# PowerSchem.net
KiCad netlist of a schematic drawn in Altium Designer
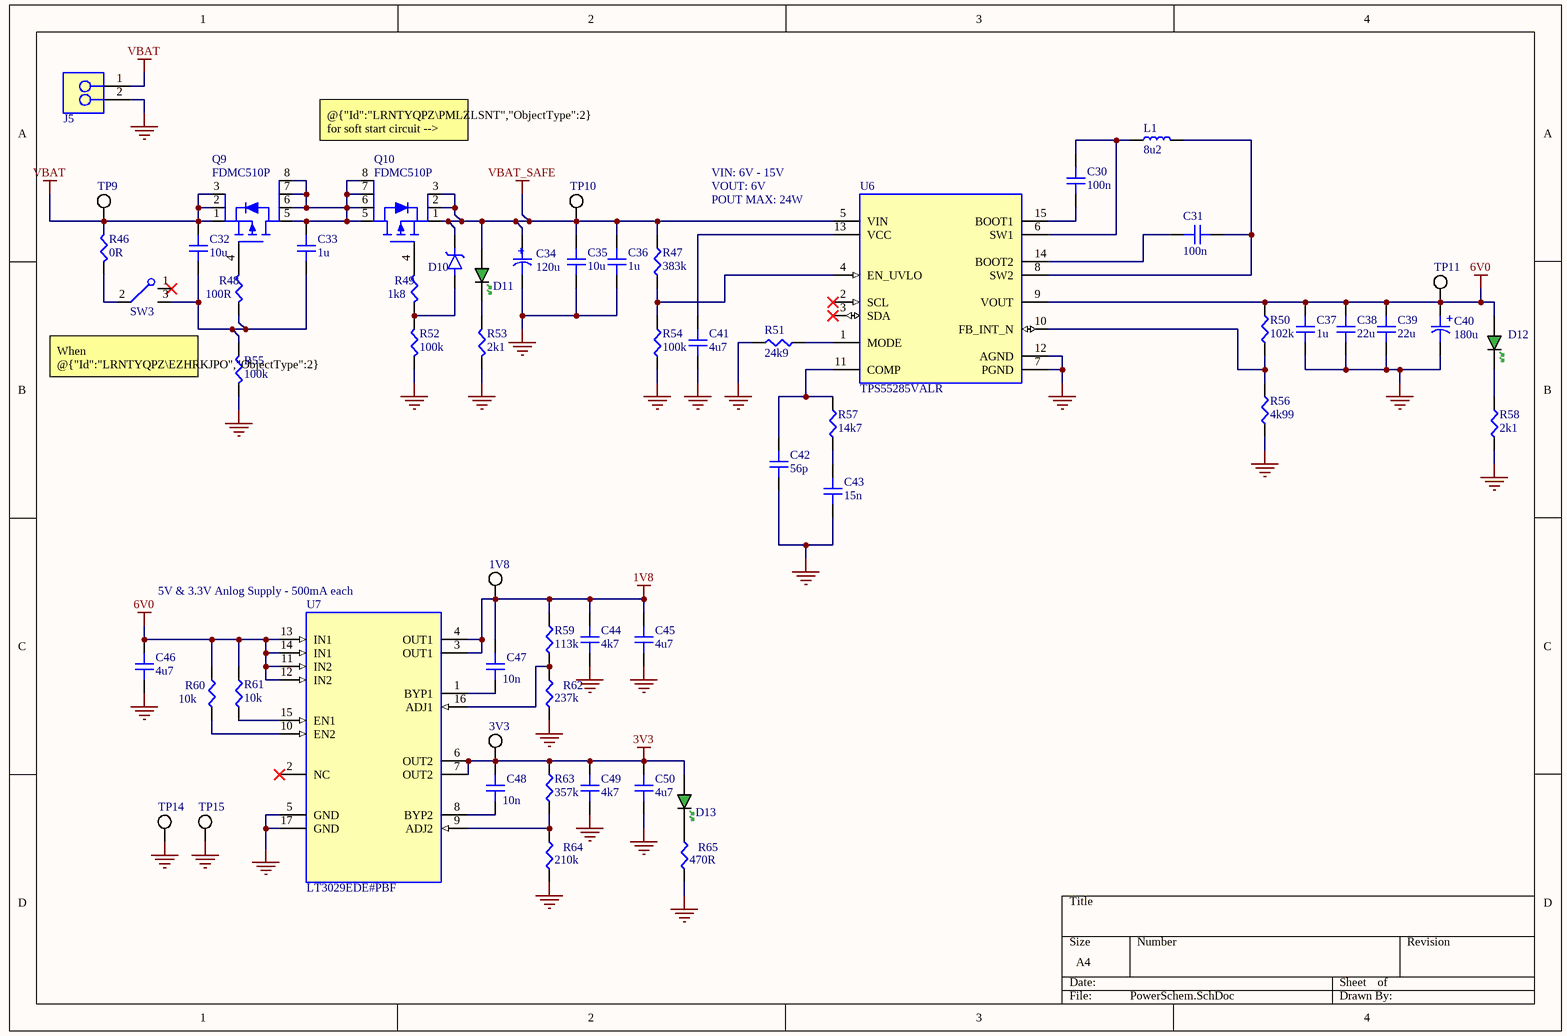
[diagram p0: PowerSchem.SchDoc]

(export (version "E")
  (design (tool "Eeschema 10.0.6"))
  (components
    (comp (ref "C30")
      (value "100n")
      (footprint "CAP_0603")
      (description "50V 100nF X7R ±10% 0603 Multilayer Ceramic Capacitors MLCC - SMD/SMT ROHS")
      (fields
        (field (name "MANUFACTURER") "Yageo Group")
        (field (name "MANUFACTURER PART NUMBER") "C0603C104K5RACTU")
      )
      (libsource (lib "Standard") (part "CAP"))
    )
    (comp (ref "C31")
      (value "100n")
      (footprint "CAP_0603")
      (description "50V 100nF X7R ±10% 0603 Multilayer Ceramic Capacitors MLCC - SMD/SMT ROHS")
      (fields (field (name "VOLTAGE") "50V") (field (name "MANUFACTURER") "Yageo Group"))
      (libsource (lib "Standard") (part "CAP"))
    )
    (comp (ref "C32")
      (value "10u")
      (footprint "CAP_0805")
      (description "25V 10uF X5R ±20% 0805 Multilayer Ceramic Capacitors MLCC - SMD/SMT ROHS")
      (fields
        (field (name "MANUFACTURER") "Murata")
        (field (name "MANUFACTURER PART NUMBER") "GRM21BR61E106MA73L")
      )
      (libsource (lib "Standard") (part "CAP"))
    )
    (comp (ref "C33")
      (value "1u")
      (footprint "CAP_0603")
      (description "25V 1uF X7R 卤10% 0603 Multilayer Ceramic Capacitors MLCC - SMD/SMT ROHS")
      (fields
        (field (name "MANUFACTURER") "Samsung Electro-Mechanics")
        (field (name "MANUFACTURER PART NUMBER") "CL10B105KA8NNNC")
      )
      (libsource (lib "Standard") (part "CAP"))
    )
    (comp (ref "C34")
      (value "120u")
      (footprint "PCAP_SVP_C6_PAN-M")
      (description "Cap Aluminum Polymer 120uF 20VDC 20%( 6.3 X 5.9mm) SMD 0.025 Ohm 3.2A 5000h 105C T/R")
      (fields
        (field (name "MANUFACTURER") "Panasonic")
        (field (name "MANUFACTURER PART NUMBER") "20SVPF120M")
      )
      (libsource (lib "") (part "CAP_ELECTROLYTIC_1"))
    )
    (comp (ref "C35")
      (value "10u")
      (footprint "CAP_0805")
      (description "25V 10uF X5R ±20% 0805 Multilayer Ceramic Capacitors MLCC - SMD/SMT ROHS")
      (fields
        (field (name "MANUFACTURER") "Murata")
        (field (name "MANUFACTURER PART NUMBER") "GRM21BR61E106MA73L")
      )
      (libsource (lib "Standard") (part "CAP"))
    )
    (comp (ref "C36")
      (value "1u")
      (footprint "CAP_0603")
      (description "25V 1uF X7R 卤10% 0603 Multilayer Ceramic Capacitors MLCC - SMD/SMT ROHS")
      (fields
        (field (name "MANUFACTURER") "Samsung Electro-Mechanics")
        (field (name "MANUFACTURER PART NUMBER") "CL10B105KA8NNNC")
      )
      (libsource (lib "Standard") (part "CAP"))
    )
    (comp (ref "C37")
      (value "1u")
      (footprint "CAP_0603")
      (description "25V 1uF X7R 卤10% 0603 Multilayer Ceramic Capacitors MLCC - SMD/SMT ROHS")
      (fields
        (field (name "MANUFACTURER") "Samsung Electro-Mechanics")
        (field (name "MANUFACTURER PART NUMBER") "CL10B105KA8NNNC")
      )
      (libsource (lib "Standard") (part "CAP"))
    )
    (comp (ref "C38")
      (value "22u")
      (footprint "CAP_0805")
      (description "25V 22uF X5R 卤20% 0805 Multilayer Ceramic Capacitors MLCC - SMD/SMT ROHS")
      (fields
        (field (name "MANUFACTURER") "Samsung Electro-Mechanics")
        (field (name "MANUFACTURER PART NUMBER") "CL21A226MAYNNNE")
      )
      (libsource (lib "Standard") (part "CAP"))
    )
    (comp (ref "C39")
      (value "22u")
      (footprint "CAP_0805")
      (description "25V 22uF X5R 卤20% 0805 Multilayer Ceramic Capacitors MLCC - SMD/SMT ROHS")
      (fields
        (field (name "MANUFACTURER") "Samsung Electro-Mechanics")
        (field (name "MANUFACTURER PART NUMBER") "CL21A226MAYNNNE")
      )
      (libsource (lib "Standard") (part "CAP"))
    )
    (comp (ref "C40")
      (value "180u")
      (footprint "PCAP_SVP_C6_PAN-M")
      (description "Cap Aluminum Polymer 180uF 16VDC 20%( 6.3 X 5.9mm) SMD 0.022 Ohm 3.3A 5000h 105C T/R")
      (fields
        (field (name "MANUFACTURER") "Panasonic")
        (field (name "MANUFACTURER PART NUMBER") "16SVPF180M")
      )
      (libsource (lib "Standard") (part "CAP_ELECTROLYTIC"))
    )
    (comp (ref "C41")
      (value "4u7")
      (footprint "CAP_0603")
      (description "25V 4.7uF X6S ±10% 0603 Multilayer Ceramic Capacitors MLCC - SMD/SMT ROHS")
      (fields
        (field (name "MANUFACTURER") "Murata")
        (field (name "MANUFACTURER PART NUMBER") "GRT188C81E475KE13D")
      )
      (libsource (lib "Standard") (part "CAP"))
    )
    (comp (ref "C42")
      (value "56p")
      (footprint "CAP_0603")
      (fields
        (field (name "MANUFACTURER") "Knowles")
        (field (name "MANUFACTURER PART NUMBER") "QSCP251Q560J1GV001T")
      )
      (libsource (lib "Standard") (part "CAP"))
    )
    (comp (ref "C43")
      (value "15n")
      (footprint "CAP_0603")
      (description "0603 C 15NF Ceramic Multilayer Capacitor, 25 V, +125DEGC, C0G Dielectric, +/-5%")
      (fields
        (field (name "MANUFACTURER") "Yageo Group")
        (field (name "MANUFACTURER PART NUMBER") "C0603C153J3GACTU")
      )
      (libsource (lib "Standard") (part "CAP"))
    )
    (comp (ref "C44")
      (value "4k7")
      (footprint "CAP_0603")
      (description "25V 4.7uF X6S ±10% 0603 Multilayer Ceramic Capacitors MLCC - SMD/SMT ROHS")
      (fields
        (field (name "MANUFACTURER") "Murata")
        (field (name "MANUFACTURER PART NUMBER") "GRT188C81E475KE13D")
      )
      (libsource (lib "Passives") (part "CAP"))
    )
    (comp (ref "C45")
      (value "4u7")
      (footprint "CAP_0603")
      (description "25V 4.7uF X6S ±10% 0603 Multilayer Ceramic Capacitors MLCC - SMD/SMT ROHS")
      (fields
        (field (name "MANUFACTURER") "Murata")
        (field (name "MANUFACTURER PART NUMBER") "GRT188C81E475KE13D")
      )
      (libsource (lib "Passives") (part "CAP"))
    )
    (comp (ref "C46")
      (value "4u7")
      (footprint "CAP_0603")
      (description "25V 4.7uF X6S ±10% 0603 Multilayer Ceramic Capacitors MLCC - SMD/SMT ROHS")
      (fields
        (field (name "MANUFACTURER") "Murata")
        (field (name "MANUFACTURER PART NUMBER") "GRT188C81E475KE13D")
      )
      (libsource (lib "Passives") (part "CAP"))
    )
    (comp (ref "C47")
      (value "10n")
      (footprint "CAP_0603")
      (description "Multilayer Ceramic Capacitors Mlcc - Smd/Smt 50V 0.01Uf X7R 0603 10%")
      (fields
        (field (name "MANUFACTURER") "Yageo Group")
        (field (name "MANUFACTURER PART NUMBER") "C0603C103K5RACTU")
      )
      (libsource (lib "Passives") (part "CAP"))
    )
    (comp (ref "C48")
      (value "10n")
      (footprint "CAP_0603")
      (description "Multilayer Ceramic Capacitors Mlcc - Smd/Smt 50V 0.01Uf X7R 0603 10%")
      (fields
        (field (name "MANUFACTURER") "Yageo Group")
        (field (name "MANUFACTURER PART NUMBER") "C0603C103K5RACTU")
      )
      (libsource (lib "Passives") (part "CAP"))
    )
    (comp (ref "C49")
      (value "4k7")
      (footprint "CAP_0603")
      (description "25V 4.7uF X6S ±10% 0603 Multilayer Ceramic Capacitors MLCC - SMD/SMT ROHS")
      (fields
        (field (name "MANUFACTURER") "Murata")
        (field (name "MANUFACTURER PART NUMBER") "GRT188C81E475KE13D")
      )
      (libsource (lib "Passives") (part "CAP"))
    )
    (comp (ref "C50")
      (value "4u7")
      (footprint "CAP_0603")
      (description "25V 4.7uF X6S ±10% 0603 Multilayer Ceramic Capacitors MLCC - SMD/SMT ROHS")
      (fields
        (field (name "MANUFACTURER") "Murata")
        (field (name "MANUFACTURER PART NUMBER") "GRT188C81E475KE13D")
      )
      (libsource (lib "Passives") (part "CAP"))
    )
    (comp (ref "D10")
      (value "65pF")
      (footprint "SOD-923")
      (description "ESD9X5.0ST5G Series 6.2 V 65 pF TVS Diode for ESD Protection - SOD-923")
      (fields (field (name "MANUFACTURER") "onsemi") (field (name "MANUFACTURER PART NUMBER") "ESD9X5.0ST5G"))
      (libsource (lib "Diodes") (part "Zenner"))
    )
    (comp (ref "D11")
      (value "LED_Green")
      (footprint "LED_0603")
      (description "LED yellow green 0603 wavelength 567.5~576.5nm light intensity 4.5~28mcd Front Mounting")
      (fields
        (field (name "MANUFACTURER") "Diodes Inc.")
        (field (name "MANUFACTURER PART NUMBER") "LTST-C193KGKT-5A")
      )
      (libsource (lib "Standard") (part "LED_Green"))
    )
    (comp (ref "D12")
      (value "LED_Green")
      (footprint "LED_0603")
      (description "LED yellow green 0603 wavelength 567.5~576.5nm light intensity 4.5~28mcd Front Mounting")
      (fields
        (field (name "MANUFACTURER") "Diodes Inc.")
        (field (name "MANUFACTURER PART NUMBER") "LTST-C193KGKT-5A")
      )
      (libsource (lib "Standard") (part "LED_Green"))
    )
    (comp (ref "D13")
      (value "LED_Green")
      (footprint "LED_0603")
      (description "LED yellow green 0603 wavelength 567.5~576.5nm light intensity 4.5~28mcd Front Mounting")
      (fields
        (field (name "MANUFACTURER") "Diodes Inc.")
        (field (name "MANUFACTURER PART NUMBER") "LTST-C193KGKT-5A")
      )
      (libsource (lib "Standard") (part "LED_Green"))
    )
    (comp (ref "J5")
      (value "2POS")
      (footprint "JST_B2B-XH-A")
      (description "Board Connector, 2 Contact(s), 1 Row(s), Male, Straight, Solder Terminal")
      (fields (field (name "MANUFACTURER") "JST") (field (name "MANUFACTURER PART NUMBER") "B2B-XH-A"))
      (libsource (lib "Connectors") (part "2POS"))
    )
    (comp (ref "L1")
      (value "8u2")
      (footprint "IND_SRP1265A-6R8M")
      (description "Ind Power Shielded Wirewound 8.2uH 20% 100kHz Metal Alloy Powder 8A (6.6 X 6.4 X 5.8mm) T/R")
      (fields
        (field (name "MANUFACTURER") "Bourns")
        (field (name "MANUFACTURER PART NUMBER") "SRP6060FA-8R2M")
      )
      (libsource (lib "Standard") (part "IND_FIXED"))
    )
    (comp (ref "Q9")
      (value "FDMC510P")
      (footprint "WDFN8_3.3X3.3")
      (description "Single P-Channel 20 V 17 mOhm 116 nC 41 W PowerTrench SMT Mosfet - MLP-3.3x3.3")
      (fields (field (name "MANUFACTURER") "onsemi"))
      (libsource (lib "Diodes") (part "PMOS"))
    )
    (comp (ref "Q10")
      (value "FDMC510P")
      (footprint "WDFN8_3.3X3.3")
      (description "Single P-Channel 20 V 17 mOhm 116 nC 41 W PowerTrench SMT Mosfet - MLP-3.3x3.3")
      (fields (field (name "MANUFACTURER") "onsemi"))
      (libsource (lib "Diodes") (part "PMOS"))
    )
    (comp (ref "R46")
      (value "0R")
      (footprint "RES_0603")
      (description "GENERAL PURPOSE CHIP RESISTOR Metal Glaze/thick Film, 0.1W, 0ohm, Surface Mount, 0603")
      (fields
        (field (name "MANUFACTURER") "Yageo Group")
        (field (name "MANUFACTURER PART NUMBER") "RC0603JR-070RL")
      )
      (libsource (lib "Passives") (part "RES"))
    )
    (comp (ref "R47")
      (value "383k")
      (footprint "RES_0603")
      (description "Res Thick Film 0603 383K Ohm 1% 0.1W(1/10W) ±100ppm/C Pad SMD T/R")
      (fields
        (field (name "MANUFACTURER") "Yageo Group")
        (field (name "MANUFACTURER PART NUMBER") "RC0603FR-07383KL")
      )
      (libsource (lib "Standard") (part "RES"))
    )
    (comp (ref "R48")
      (value "100R")
      (footprint "RES_0603")
      (description "Yageo RC0603FR-07100RL 0603 SMD Resistor 100 Ohm thin film chip resistor")
      (fields
        (field (name "MANUFACTURER") "Yageo Group")
        (field (name "MANUFACTURER PART NUMBER") "RC0603FR-07100RL")
      )
      (libsource (lib "Passives") (part "RES"))
    )
    (comp (ref "R49")
      (value "1k8")
      (footprint "RES_0603")
      (description "General Purpose Chip Resistors RC0603 Rohs Compliant ¦ Res SMD 1.8K Ohm 1% 1/10W 0603")
      (fields
        (field (name "MANUFACTURER") "Yageo Group")
        (field (name "MANUFACTURER PART NUMBER") "RC0603FR-071K8L")
      )
      (libsource (lib "Passives") (part "RES"))
    )
    (comp (ref "R50")
      (value "102k")
      (footprint "RES_0603")
      (description "100mW Thin Film Resistor ±25ppm/℃ ±0.1% 102kΩ 0603 Chip Resistor - Surface Mount ROHS")
      (fields
        (field (name "MANUFACTURER") "Yageo Group")
        (field (name "MANUFACTURER PART NUMBER") "RT0603BRD07102KL")
      )
      (libsource (lib "Standard") (part "RES"))
    )
    (comp (ref "R51")
      (value "24k9")
      (footprint "RES_0603")
      (description "Res Thick Film 0603 24.9K Ohm 1% 1/10W ¦100ppm/¦C SMD Punched Carrier T/R")
      (fields
        (field (name "MANUFACTURER") "Panasonic")
        (field (name "MANUFACTURER PART NUMBER") "ERJ-3EKF2492V")
      )
      (libsource (lib "Standard") (part "RES"))
    )
    (comp (ref "R52")
      (value "100k")
      (footprint "RES_0603")
      (description "Yageo RC0603FR-07100KL resistor 100k ohm 0603 1% thick film surface mount")
      (fields
        (field (name "MANUFACTURER") "Bourns")
        (field (name "MANUFACTURER PART NUMBER") "CR0603-FX-1003ELF")
      )
      (libsource (lib "Passives") (part "RES"))
    )
    (comp (ref "R53")
      (value "2k1")
      (footprint "RES_0603")
      (description "Res Thick Film 0603 2.1K Ohm 1% 0.1W(1/10W) ±100ppm/C Pad SMD T/R")
      (fields
        (field (name "MANUFACTURER") "Yageo Group")
        (field (name "MANUFACTURER PART NUMBER") "RC0603FR-072K1L")
      )
      (libsource (lib "Passives") (part "RES"))
    )
    (comp (ref "R54")
      (value "100k")
      (footprint "RES_0603")
      (description "Yageo RC0603FR-07100KL resistor 100k ohm 0603 1% thick film surface mount")
      (fields
        (field (name "MANUFACTURER") "Yageo Group")
        (field (name "MANUFACTURER PART NUMBER") "RC0603FR-07100KL")
      )
      (libsource (lib "Standard") (part "RES"))
    )
    (comp (ref "R55")
      (value "100k")
      (footprint "RES_0603")
      (description "Yageo RC0603FR-07100KL resistor 100k ohm 0603 1% thick film surface mount")
      (fields
        (field (name "MANUFACTURER") "Yageo Group")
        (field (name "MANUFACTURER PART NUMBER") "RC0603FR-07100KL")
      )
      (libsource (lib "Passives") (part "RES"))
    )
    (comp (ref "R56")
      (value "4k99")
      (footprint "RES_0603")
      (description "100mW Thick Film Resistors 75V ±100ppm/℃ ±1% 4.99kΩ 0603 Chip Resistor - Surface Mount ROHS")
      (fields
        (field (name "MANUFACTURER") "Yageo Group")
        (field (name "MANUFACTURER PART NUMBER") "RC0603FR-074K99L")
      )
      (libsource (lib "Standard") (part "RES"))
    )
    (comp (ref "R57")
      (value "14k7")
      (footprint "RES_0603")
      (description "Res Thick Film 0603 14.7K Ohm 1% 0.1W(1/10W) ±100ppm/C Pad SMD T/R Automotive AEC-Q200")
      (fields
        (field (name "MANUFACTURER") "Stackpole Electronics")
        (field (name "MANUFACTURER PART NUMBER") "RMCF0603FT14K7")
      )
      (libsource (lib "Standard") (part "RES"))
    )
    (comp (ref "R58")
      (value "2k1")
      (footprint "RES_0603")
      (description "Res Thick Film 0603 2.1K Ohm 1% 0.1W(1/10W) ±100ppm/C Pad SMD T/R")
      (fields
        (field (name "MANUFACTURER") "Yageo Group")
        (field (name "MANUFACTURER PART NUMBER") "RC0603FR-072K1L")
      )
      (libsource (lib "Standard") (part "RES"))
    )
    (comp (ref "R59")
      (value "113k")
      (footprint "RES_0603")
      (description "100mW Thick Film Resistors 75V ±100ppm/℃ ±1% 113kΩ 0603 Chip Resistor - Surface Mount ROHS")
      (fields
        (field (name "MANUFACTURER") "Yageo Group")
        (field (name "MANUFACTURER PART NUMBER") "RC0603FR-07113KL")
      )
      (libsource (lib "Passives") (part "RES"))
    )
    (comp (ref "R60")
      (value "10k")
      (footprint "RES_0603")
      (description "100mW Thick Film Resistors ±100ppm/℃ ±1% 10kΩ 0603 Chip Resistor - Surface Mount ROHS")
      (fields
        (field (name "MANUFACTURER") "Yageo Group")
        (field (name "MANUFACTURER PART NUMBER") "RC0603FR-0710KL")
      )
      (libsource (lib "Passives") (part "RES"))
    )
    (comp (ref "R61")
      (value "10k")
      (footprint "RES_0603")
      (description "100mW Thick Film Resistors ±100ppm/℃ ±1% 10kΩ 0603 Chip Resistor - Surface Mount ROHS")
      (fields
        (field (name "MANUFACTURER") "Yageo Group")
        (field (name "MANUFACTURER PART NUMBER") "RC0603FR-0710KL")
      )
      (libsource (lib "Passives") (part "RES"))
    )
    (comp (ref "R62")
      (value "237k")
      (footprint "RES_0603")
      (description "Res Thick Film 0603 237K Ohm 1% 0.1W(1/10W) ±100ppm/C Pad SMD Automotive T/R")
      (fields
        (field (name "MANUFACTURER") "Yageo Group")
        (field (name "MANUFACTURER PART NUMBER") "AC0603FR-07237KL")
      )
      (libsource (lib "Passives") (part "RES"))
    )
    (comp (ref "R63")
      (value "357k")
      (footprint "RES_0603")
      (description "Fixed Resistor, Thin Film, 0.1W, 357000ohm, 75V, 0.1% +/-Tol, 25ppm/Cel, Surface Mount, 0603")
      (fields
        (field (name "MANUFACTURER") "Yageo Group")
        (field (name "MANUFACTURER PART NUMBER") "RT0603BRD07357KL")
      )
      (libsource (lib "Passives") (part "RES"))
    )
    (comp (ref "R64")
      (value "210k")
      (footprint "RES_0603")
      (description "100mW Thick Film Resistors 75V ±100ppm/℃ ±1% 210kΩ 0603 Chip Resistor - Surface Mount ROHS")
      (fields
        (field (name "MANUFACTURER") "Yageo Group")
        (field (name "MANUFACTURER PART NUMBER") "RC0603FR-07210KL")
      )
      (libsource (lib "Passives") (part "RES"))
    )
    (comp (ref "R65")
      (value "470R")
      (footprint "RES_0603")
      (description "Res Thick Film 0603 470 Ohm 1% 0.1W(1/10W) ±100ppm/C Pad SMD T/R")
      (fields
        (field (name "MANUFACTURER") "Yageo Group")
        (field (name "MANUFACTURER PART NUMBER") "RC0603FR-07470RL")
      )
      (libsource (lib "Passives") (part "RES"))
    )
    (comp (ref "SW3")
      (value "SW_SPDT")
      (footprint "OS102011MA1QN1_CNK")
      (description "Switch Slide ON ON SPDT Side Slide 0.1A 12VDC 10000Cycle PC Pins Thru-Hole Bulk")
      (fields
        (field (name "MANUFACTURER") "C&K Components")
        (field (name "MANUFACTURER PART NUMBER") "OS102011MA1QN1")
      )
      (libsource (lib "Standard") (part "SW_SPDT"))
    )
    (comp (ref "TP9") (value "GND") (footprint "TP-TH") (libsource (lib "Passives") (part "TP")))
    (comp (ref "TP10") (value "GND") (footprint "TP-TH") (libsource (lib "Passives") (part "TP")))
    (comp (ref "TP11") (value "GND") (footprint "TP-TH") (libsource (lib "Passives") (part "TP")))
    (comp (ref "TP12") (value "1V8") (footprint "TP-TH") (libsource (lib "Passives") (part "TP")))
    (comp (ref "TP13") (value "3V3") (footprint "TP-TH") (libsource (lib "Passives") (part "TP")))
    (comp (ref "TP14") (value "GND") (footprint "TP-TH") (libsource (lib "Passives") (part "TP")))
    (comp (ref "TP15") (value "GND") (footprint "TP-TH") (libsource (lib "Passives") (part "TP")))
    (comp (ref "U6")
      (value "TPS55285VALR")
      (footprint "WQFN-HF(VAL)")
      (description "22V 8A buck-boost converter with I²C interface 15-WQFN-HR -40 to 125")
      (fields
        (field (name "MANUFACTURER_PART_NUMBER") "XTPS55285VALR")
        (field (name "MANUFACTURER") "Texas Instruments")
        (field (name "COPYRIGHT") "Copyright (C) 2026 Ultra Librarian. All rights reserved.")
      )
      (libsource (lib "Power") (part "XTPS55285VALR"))
    )
    (comp (ref "U7")
      (value "LT3029EDE#PBF")
      (footprint "MSOP-16_MSE")
      (description "LDO Regulator Pos 1.215V to 19.5V 0.5A 16-Pin DFN EP")
      (fields (field (name "MANUFACTURER") "Analog Devices"))
      (libsource (lib "Power") (part "LT3029EDE#PBF"))
    )
  )
  (nets
    (net (code "1") (name "1V8") (class "Default")
      (node (ref "C44") (pin "2") (pinfunction "2_2") (pintype "passive"))
      (node (ref "C45") (pin "2") (pinfunction "2_2") (pintype "passive"))
      (node (ref "C47") (pin "2") (pinfunction "2_2") (pintype "passive"))
      (node (ref "R59") (pin "2") (pinfunction "2_2") (pintype "passive"))
      (node (ref "TP12") (pin "1") (pinfunction "1_1") (pintype "passive"))
      (node (ref "U7") (pin "3") (pinfunction "OUT1_3") (pintype "power_in"))
      (node (ref "U7") (pin "4") (pinfunction "OUT1_4") (pintype "power_in"))
    )
    (net (code "2") (name "3V3") (class "Default")
      (node (ref "C48") (pin "2") (pinfunction "2_2") (pintype "passive"))
      (node (ref "C49") (pin "2") (pinfunction "2_2") (pintype "passive"))
      (node (ref "C50") (pin "2") (pinfunction "2_2") (pintype "passive"))
      (node (ref "D13") (pin "2") (pinfunction "Anode_2") (pintype "passive"))
      (node (ref "R63") (pin "2") (pinfunction "2_2") (pintype "passive"))
      (node (ref "TP13") (pin "1") (pinfunction "1_1") (pintype "passive"))
      (node (ref "U7") (pin "6") (pinfunction "OUT2_6") (pintype "power_in"))
      (node (ref "U7") (pin "7") (pinfunction "OUT2_7") (pintype "power_in"))
    )
    (net (code "3") (name "6V0") (class "Default")
      (node (ref "C37") (pin "2") (pinfunction "2_2") (pintype "passive"))
      (node (ref "C38") (pin "2") (pinfunction "2_2") (pintype "passive"))
      (node (ref "C39") (pin "2") (pinfunction "2_2") (pintype "passive"))
      (node (ref "C40") (pin "1") (pinfunction "1_1") (pintype "passive"))
      (node (ref "C46") (pin "2") (pinfunction "2_2") (pintype "passive"))
      (node (ref "D12") (pin "2") (pinfunction "Anode_2") (pintype "passive"))
      (node (ref "R50") (pin "2") (pinfunction "2_2") (pintype "passive"))
      (node (ref "R60") (pin "2") (pinfunction "2_2") (pintype "passive"))
      (node (ref "R61") (pin "2") (pinfunction "2_2") (pintype "passive"))
      (node (ref "TP11") (pin "1") (pinfunction "1_1") (pintype "passive"))
      (node (ref "U6") (pin "9") (pinfunction "VOUT_9") (pintype "passive"))
      (node (ref "U7") (pin "11") (pinfunction "IN2_11") (pintype "input"))
      (node (ref "U7") (pin "12") (pinfunction "IN2_12") (pintype "input"))
      (node (ref "U7") (pin "13") (pinfunction "IN1_13") (pintype "input"))
      (node (ref "U7") (pin "14") (pinfunction "IN1_14") (pintype "input"))
    )
    (net (code "4") (name "GND") (class "Default")
      (node (ref "C34") (pin "2") (pinfunction "2_2") (pintype "passive"))
      (node (ref "C35") (pin "1") (pinfunction "1_1") (pintype "passive"))
      (node (ref "C36") (pin "1") (pinfunction "1_1") (pintype "passive"))
      (node (ref "C37") (pin "1") (pinfunction "1_1") (pintype "passive"))
      (node (ref "C38") (pin "1") (pinfunction "1_1") (pintype "passive"))
      (node (ref "C39") (pin "1") (pinfunction "1_1") (pintype "passive"))
      (node (ref "C40") (pin "2") (pinfunction "2_2") (pintype "passive"))
      (node (ref "C41") (pin "1") (pinfunction "1_1") (pintype "passive"))
      (node (ref "C42") (pin "1") (pinfunction "1_1") (pintype "passive"))
      (node (ref "C43") (pin "1") (pinfunction "1_1") (pintype "passive"))
      (node (ref "C44") (pin "1") (pinfunction "1_1") (pintype "passive"))
      (node (ref "C45") (pin "1") (pinfunction "1_1") (pintype "passive"))
      (node (ref "C46") (pin "1") (pinfunction "1_1") (pintype "passive"))
      (node (ref "C49") (pin "1") (pinfunction "1_1") (pintype "passive"))
      (node (ref "C50") (pin "1") (pinfunction "1_1") (pintype "passive"))
      (node (ref "J5") (pin "2") (pinfunction "2_2") (pintype "passive"))
      (node (ref "R51") (pin "2") (pinfunction "2_2") (pintype "passive"))
      (node (ref "R52") (pin "1") (pinfunction "1_1") (pintype "passive"))
      (node (ref "R53") (pin "1") (pinfunction "1_1") (pintype "passive"))
      (node (ref "R54") (pin "1") (pinfunction "1_1") (pintype "passive"))
      (node (ref "R55") (pin "1") (pinfunction "1_1") (pintype "passive"))
      (node (ref "R56") (pin "1") (pinfunction "1_1") (pintype "passive"))
      (node (ref "R58") (pin "1") (pinfunction "1_1") (pintype "passive"))
      (node (ref "R62") (pin "1") (pinfunction "1_1") (pintype "passive"))
      (node (ref "R64") (pin "1") (pinfunction "1_1") (pintype "passive"))
      (node (ref "R65") (pin "1") (pinfunction "1_1") (pintype "passive"))
      (node (ref "TP14") (pin "1") (pinfunction "1_1") (pintype "passive"))
      (node (ref "TP15") (pin "1") (pinfunction "1_1") (pintype "passive"))
      (node (ref "U6") (pin "12") (pinfunction "AGND_12") (pintype "power_in"))
      (node (ref "U6") (pin "7") (pinfunction "PGND_7") (pintype "power_in"))
      (node (ref "U7") (pin "17") (pinfunction "GND_17") (pintype "passive"))
      (node (ref "U7") (pin "5") (pinfunction "GND_5") (pintype "passive"))
    )
    (net (code "5") (name "Net-(C33-Pad2)") (class "Default")
      (node (ref "C33") (pin "2") (pinfunction "2_2") (pintype "passive"))
      (node (ref "Q10") (pin "5") (pinfunction "Drain_5") (pintype "passive"))
      (node (ref "Q10") (pin "6") (pinfunction "Drain_6") (pintype "passive"))
      (node (ref "Q10") (pin "7") (pinfunction "Drain_7") (pintype "passive"))
      (node (ref "Q10") (pin "8") (pinfunction "Drain_8") (pintype "passive"))
      (node (ref "Q9") (pin "5") (pinfunction "Drain_5") (pintype "passive"))
      (node (ref "Q9") (pin "6") (pinfunction "Drain_6") (pintype "passive"))
      (node (ref "Q9") (pin "7") (pinfunction "Drain_7") (pintype "passive"))
      (node (ref "Q9") (pin "8") (pinfunction "Drain_8") (pintype "passive"))
    )
    (net (code "6") (name "Net-(C43-Pad2)") (class "Default")
      (node (ref "C43") (pin "2") (pinfunction "2_2") (pintype "passive"))
      (node (ref "R57") (pin "1") (pinfunction "1_1") (pintype "passive"))
    )
    (net (code "7") (name "Net-(D10-Pad2)") (class "Default")
      (node (ref "D10") (pin "2") (pinfunction "2_2") (pintype "passive"))
      (node (ref "R49") (pin "1") (pinfunction "1_1") (pintype "passive"))
      (node (ref "R52") (pin "2") (pinfunction "2_2") (pintype "passive"))
    )
    (net (code "8") (name "Net-(D11-Cathode)") (class "Default")
      (node (ref "D11") (pin "1") (pinfunction "Cathode_1") (pintype "passive"))
      (node (ref "R53") (pin "2") (pinfunction "2_2") (pintype "passive"))
    )
    (net (code "9") (name "Net-(D12-Cathode)") (class "Default")
      (node (ref "D12") (pin "1") (pinfunction "Cathode_1") (pintype "passive"))
      (node (ref "R58") (pin "2") (pinfunction "2_2") (pintype "passive"))
    )
    (net (code "10") (name "Net-(D13-Cathode)") (class "Default")
      (node (ref "D13") (pin "1") (pinfunction "Cathode_1") (pintype "passive"))
      (node (ref "R65") (pin "2") (pinfunction "2_2") (pintype "passive"))
    )
    (net (code "11") (name "Net-(Q9-Gate)") (class "Default")
      (node (ref "Q9") (pin "4") (pinfunction "Gate_4") (pintype "passive"))
      (node (ref "R48") (pin "2") (pinfunction "2_2") (pintype "passive"))
    )
    (net (code "12") (name "Net-(Q10-Gate)") (class "Default")
      (node (ref "Q10") (pin "4") (pinfunction "Gate_4") (pintype "passive"))
      (node (ref "R49") (pin "2") (pinfunction "2_2") (pintype "passive"))
    )
    (net (code "13") (name "Net-(SW3-13)") (class "Default")
      (node (ref "R46") (pin "1") (pinfunction "1_1") (pintype "passive"))
      (node (ref "SW3") (pin "2") (pinfunction "13_2") (pintype "passive"))
    )
    (net (code "14") (name "Net-(SW3-14)") (class "Default")
      (node (ref "C32") (pin "1") (pinfunction "1_1") (pintype "passive"))
      (node (ref "C33") (pin "1") (pinfunction "1_1") (pintype "passive"))
      (node (ref "R48") (pin "1") (pinfunction "1_1") (pintype "passive"))
      (node (ref "R55") (pin "2") (pinfunction "2_2") (pintype "passive"))
      (node (ref "SW3") (pin "3") (pinfunction "14_3") (pintype "passive"))
    )
    (net (code "15") (name "Net-(U6-BOOT1)") (class "Default")
      (node (ref "C30") (pin "1") (pinfunction "1_1") (pintype "passive"))
      (node (ref "U6") (pin "15") (pinfunction "BOOT1_15") (pintype "power_in"))
    )
    (net (code "16") (name "Net-(U6-BOOT2)") (class "Default")
      (node (ref "C31") (pin "2") (pinfunction "2_2") (pintype "passive"))
      (node (ref "U6") (pin "14") (pinfunction "BOOT2_14") (pintype "power_in"))
    )
    (net (code "17") (name "Net-(U6-COMP)") (class "Default")
      (node (ref "C42") (pin "2") (pinfunction "2_2") (pintype "passive"))
      (node (ref "R57") (pin "2") (pinfunction "2_2") (pintype "passive"))
      (node (ref "U6") (pin "11") (pinfunction "COMP_11") (pintype "passive"))
    )
    (net (code "18") (name "Net-(U6-EN_UVLO)") (class "Default")
      (node (ref "R47") (pin "1") (pinfunction "1_1") (pintype "passive"))
      (node (ref "R54") (pin "2") (pinfunction "2_2") (pintype "passive"))
      (node (ref "U6") (pin "4") (pinfunction "EN_UVLO_4") (pintype "input"))
    )
    (net (code "19") (name "Net-(U6-FB_INT_N)") (class "Default")
      (node (ref "R50") (pin "1") (pinfunction "1_1") (pintype "passive"))
      (node (ref "R56") (pin "2") (pinfunction "2_2") (pintype "passive"))
      (node (ref "U6") (pin "10") (pinfunction "FB_INT_N_10") (pintype "bidirectional"))
    )
    (net (code "20") (name "Net-(U6-MODE)") (class "Default")
      (node (ref "R51") (pin "1") (pinfunction "1_1") (pintype "passive"))
      (node (ref "U6") (pin "1") (pinfunction "MODE_1") (pintype "passive"))
    )
    (net (code "21") (name "Net-(U6-SW1)") (class "Default")
      (node (ref "C30") (pin "2") (pinfunction "2_2") (pintype "passive"))
      (node (ref "L1") (pin "1") (pinfunction "1_1") (pintype "passive"))
      (node (ref "U6") (pin "6") (pinfunction "SW1_6") (pintype "power_in"))
    )
    (net (code "22") (name "Net-(U6-SW2)") (class "Default")
      (node (ref "C31") (pin "1") (pinfunction "1_1") (pintype "passive"))
      (node (ref "L1") (pin "2") (pinfunction "2_2") (pintype "passive"))
      (node (ref "U6") (pin "8") (pinfunction "SW2_8") (pintype "power_in"))
    )
    (net (code "23") (name "Net-(U6-VCC)") (class "Default")
      (node (ref "C41") (pin "2") (pinfunction "2_2") (pintype "passive"))
      (node (ref "U6") (pin "13") (pinfunction "VCC_13") (pintype "power_in"))
    )
    (net (code "24") (name "Net-(U7-ADJ1)") (class "Default")
      (node (ref "R59") (pin "1") (pinfunction "1_1") (pintype "passive"))
      (node (ref "R62") (pin "2") (pinfunction "2_2") (pintype "passive"))
      (node (ref "U7") (pin "16") (pinfunction "ADJ1_16") (pintype "input"))
    )
    (net (code "25") (name "Net-(U7-ADJ2)") (class "Default")
      (node (ref "R63") (pin "1") (pinfunction "1_1") (pintype "passive"))
      (node (ref "R64") (pin "2") (pinfunction "2_2") (pintype "passive"))
      (node (ref "U7") (pin "9") (pinfunction "ADJ2_9") (pintype "input"))
    )
    (net (code "26") (name "Net-(U7-BYP1)") (class "Default")
      (node (ref "C47") (pin "1") (pinfunction "1_1") (pintype "passive"))
      (node (ref "U7") (pin "1") (pinfunction "BYP1_1") (pintype "passive"))
    )
    (net (code "27") (name "Net-(U7-BYP2)") (class "Default")
      (node (ref "C48") (pin "1") (pinfunction "1_1") (pintype "passive"))
      (node (ref "U7") (pin "8") (pinfunction "BYP2_8") (pintype "passive"))
    )
    (net (code "28") (name "Net-(U7-EN1)") (class "Default")
      (node (ref "R61") (pin "1") (pinfunction "1_1") (pintype "passive"))
      (node (ref "U7") (pin "15") (pinfunction "EN1_15") (pintype "input"))
    )
    (net (code "29") (name "Net-(U7-EN2)") (class "Default")
      (node (ref "R60") (pin "1") (pinfunction "1_1") (pintype "passive"))
      (node (ref "U7") (pin "10") (pinfunction "EN2_10") (pintype "input"))
    )
    (net (code "30") (name "VBAT") (class "Default")
      (node (ref "C32") (pin "2") (pinfunction "2_2") (pintype "passive"))
      (node (ref "J5") (pin "1") (pinfunction "1_1") (pintype "passive"))
      (node (ref "Q9") (pin "1") (pinfunction "Source_1") (pintype "passive"))
      (node (ref "Q9") (pin "2") (pinfunction "Source_2") (pintype "passive"))
      (node (ref "Q9") (pin "3") (pinfunction "Source_3") (pintype "passive"))
      (node (ref "R46") (pin "2") (pinfunction "2_2") (pintype "passive"))
      (node (ref "TP9") (pin "1") (pinfunction "1_1") (pintype "passive"))
    )
    (net (code "31") (name "VBAT_SAFE") (class "Default")
      (node (ref "C34") (pin "1") (pinfunction "1_1") (pintype "passive"))
      (node (ref "C35") (pin "2") (pinfunction "2_2") (pintype "passive"))
      (node (ref "C36") (pin "2") (pinfunction "2_2") (pintype "passive"))
      (node (ref "D10") (pin "1") (pinfunction "1_1") (pintype "passive"))
      (node (ref "D11") (pin "2") (pinfunction "Anode_2") (pintype "passive"))
      (node (ref "Q10") (pin "1") (pinfunction "Source_1") (pintype "passive"))
      (node (ref "Q10") (pin "2") (pinfunction "Source_2") (pintype "passive"))
      (node (ref "Q10") (pin "3") (pinfunction "Source_3") (pintype "passive"))
      (node (ref "R47") (pin "2") (pinfunction "2_2") (pintype "passive"))
      (node (ref "TP10") (pin "1") (pinfunction "1_1") (pintype "passive"))
      (node (ref "U6") (pin "5") (pinfunction "VIN_5") (pintype "power_in"))
    )
    (net (code "32") (name "unconnected-(SW3-Pad1)") (class "Default")
      (node (ref "SW3") (pin "1") (pintype "passive+no_connect"))
    )
    (net (code "33") (name "unconnected-(U6-SCL-Pad2)") (class "Default")
      (node (ref "U6") (pin "2") (pinfunction "SCL_2") (pintype "input+no_connect"))
    )
    (net (code "34") (name "unconnected-(U6-SDA-Pad3)") (class "Default")
      (node (ref "U6") (pin "3") (pinfunction "SDA_3") (pintype "bidirectional+no_connect"))
    )
    (net (code "35") (name "unconnected-(U7-NC-Pad2)") (class "Default")
      (node (ref "U7") (pin "2") (pinfunction "NC_2") (pintype "passive+no_connect"))
    )
  )
)
